# Flash.net
KiCad netlist of a schematic drawn in Altium Designer
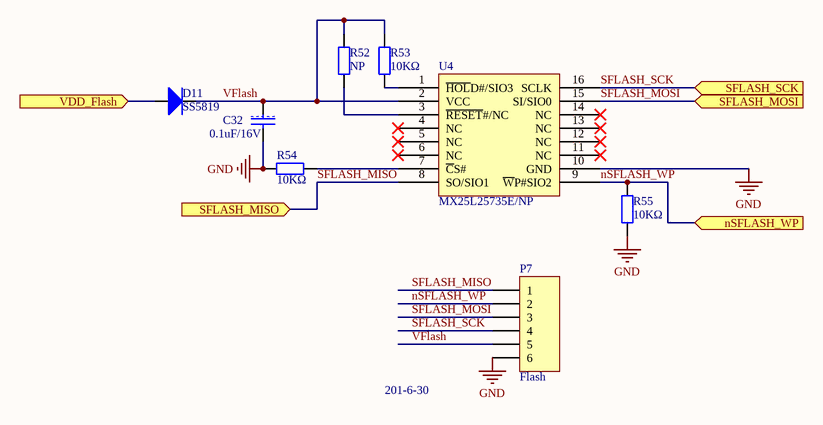
[diagram p0: Flash.SchDoc]

(export (version "E")
  (design (tool "Eeschema 10.0.6"))
  (components
    (comp (ref "C32")
      (value "0.1uF/16V")
      (footprint "0603R")
      (description "贴片陶瓷电容")
      (fields (field (name "AUTHOR") "叶建峰"))
      (libsource (lib "*") (part "CAP"))
    )
    (comp (ref "D11")
      (value "SS5819")
      (footprint "SMA")
      (description "贴片二极管")
      (fields (field (name "AUTHOR") "叶建峰"))
      (libsource (lib "Miscellaneous Devices") (part "Diode 1N914"))
    )
    (comp (ref "P7")
      (value "Flash")
      (footprint "CON6-2.0")
      (description "Header, 6-Pin")
      (fields (field (name "PUBLISHER") "Altium Limited"))
      (libsource (lib "Miscellaneous Connectors") (part "Header 6"))
    )
    (comp (ref "R52")
      (value "NP")
      (footprint "0603R")
      (libsource (lib "altium-import") (part "root_1_mirrored_RES_0603_"))
    )
    (comp (ref "R53")
      (value "10KΩ")
      (footprint "0603R")
      (libsource (lib "altium-import") (part "root_1_mirrored_RES_0603_"))
    )
    (comp (ref "R54")
      (value "10KΩ")
      (footprint "0603R")
      (libsource (lib "altium-import") (part "root_0_mirrored_RES_0603_"))
    )
    (comp (ref "R55")
      (value "10KΩ")
      (footprint "0603R")
      (libsource (lib "altium-import") (part "root_3_mirrored_RES_0603_"))
    )
    (comp (ref "U4")
      (value "MX25L25735E/NP")
      (footprint "SOIC16W")
      (description "SPI_flash")
      (fields (field (name "MANUFACTURER") "MXIC") (field (name "AUTHOR") "杨杰"))
      (libsource (lib "soooqooo_V6.0") (part "MX25L25735E"))
    )
  )
  (nets
    (net (code "1") (name "/SFLASH_MISO") (class "Default")
      (node (ref "P7") (pin "1") (pinfunction "1_1") (pintype "passive"))
      (node (ref "U4") (pin "8") (pinfunction "SO/SIO1_8") (pintype "passive"))
    )
    (net (code "2") (name "/SFLASH_MOSI") (class "Default")
      (node (ref "P7") (pin "3") (pinfunction "3_3") (pintype "passive"))
      (node (ref "U4") (pin "15") (pinfunction "SI/SIO0_15") (pintype "passive"))
    )
    (net (code "3") (name "/SFLASH_SCK") (class "Default")
      (node (ref "P7") (pin "4") (pinfunction "4_4") (pintype "passive"))
      (node (ref "U4") (pin "16") (pinfunction "SCLK_16") (pintype "passive"))
    )
    (net (code "4") (name "/VDD_Flash") (class "Default")
      (node (ref "D11") (pin "1") (pinfunction "A_1") (pintype "passive"))
    )
    (net (code "5") (name "/VFlash") (class "Default")
      (node (ref "C32") (pin "1") (pinfunction "1_1") (pintype "passive"))
      (node (ref "D11") (pin "2") (pinfunction "K_2") (pintype "passive"))
      (node (ref "P7") (pin "5") (pinfunction "5_5") (pintype "passive"))
      (node (ref "R52") (pin "2") (pinfunction "2_2") (pintype "passive"))
      (node (ref "R53") (pin "2") (pinfunction "2_2") (pintype "passive"))
      (node (ref "U4") (pin "2") (pinfunction "VCC_2") (pintype "passive"))
    )
    (net (code "6") (name "/nSFLASH_WP") (class "Default")
      (node (ref "P7") (pin "2") (pinfunction "2_2") (pintype "passive"))
      (node (ref "R55") (pin "1") (pinfunction "1_1") (pintype "passive"))
      (node (ref "U4") (pin "9") (pinfunction "~{W}P#SIO2_9") (pintype "passive"))
    )
    (net (code "7") (name "GND") (class "Default")
      (node (ref "C32") (pin "2") (pinfunction "2_2") (pintype "passive"))
      (node (ref "P7") (pin "6") (pinfunction "6_6") (pintype "passive"))
      (node (ref "R54") (pin "2") (pinfunction "2_2") (pintype "passive"))
      (node (ref "R55") (pin "2") (pinfunction "2_2") (pintype "passive"))
      (node (ref "U4") (pin "10") (pinfunction "GND_10") (pintype "passive"))
    )
    (net (code "8") (name "Net-(U4-~{C}S#)") (class "Default")
      (node (ref "R54") (pin "1") (pinfunction "1_1") (pintype "passive"))
      (node (ref "U4") (pin "7") (pinfunction "~{C}S#_7") (pintype "passive"))
    )
    (net (code "9") (name "Net-(U4-~{HOL}D#{slash}SIO3)") (class "Default")
      (node (ref "R53") (pin "1") (pinfunction "1_1") (pintype "passive"))
      (node (ref "U4") (pin "1") (pinfunction "~{HOL}D#/SIO3_1") (pintype "passive"))
    )
    (net (code "10") (name "Net-(U4-~{RESET}#{slash}NC)") (class "Default")
      (node (ref "R52") (pin "1") (pinfunction "1_1") (pintype "passive"))
      (node (ref "U4") (pin "3") (pinfunction "~{RESET}#/NC_3") (pintype "passive"))
    )
    (net (code "11") (name "unconnected-(U4-NC-Pad4)") (class "Default")
      (node (ref "U4") (pin "4") (pinfunction "NC_4") (pintype "passive+no_connect"))
    )
    (net (code "12") (name "unconnected-(U4-NC-Pad5)") (class "Default")
      (node (ref "U4") (pin "5") (pinfunction "NC_5") (pintype "passive+no_connect"))
    )
    (net (code "13") (name "unconnected-(U4-NC-Pad6)") (class "Default")
      (node (ref "U4") (pin "6") (pinfunction "NC_6") (pintype "passive+no_connect"))
    )
    (net (code "14") (name "unconnected-(U4-NC-Pad11)") (class "Default")
      (node (ref "U4") (pin "11") (pinfunction "NC_11") (pintype "passive+no_connect"))
    )
    (net (code "15") (name "unconnected-(U4-NC-Pad12)") (class "Default")
      (node (ref "U4") (pin "12") (pinfunction "NC_12") (pintype "passive+no_connect"))
    )
    (net (code "16") (name "unconnected-(U4-NC-Pad13)") (class "Default")
      (node (ref "U4") (pin "13") (pinfunction "NC_13") (pintype "passive+no_connect"))
    )
    (net (code "17") (name "unconnected-(U4-NC-Pad14)") (class "Default")
      (node (ref "U4") (pin "14") (pinfunction "NC_14") (pintype "passive+no_connect"))
    )
  )
)
